# Ethernet_Phy.net
KiCad netlist of a schematic drawn in Altium Designer
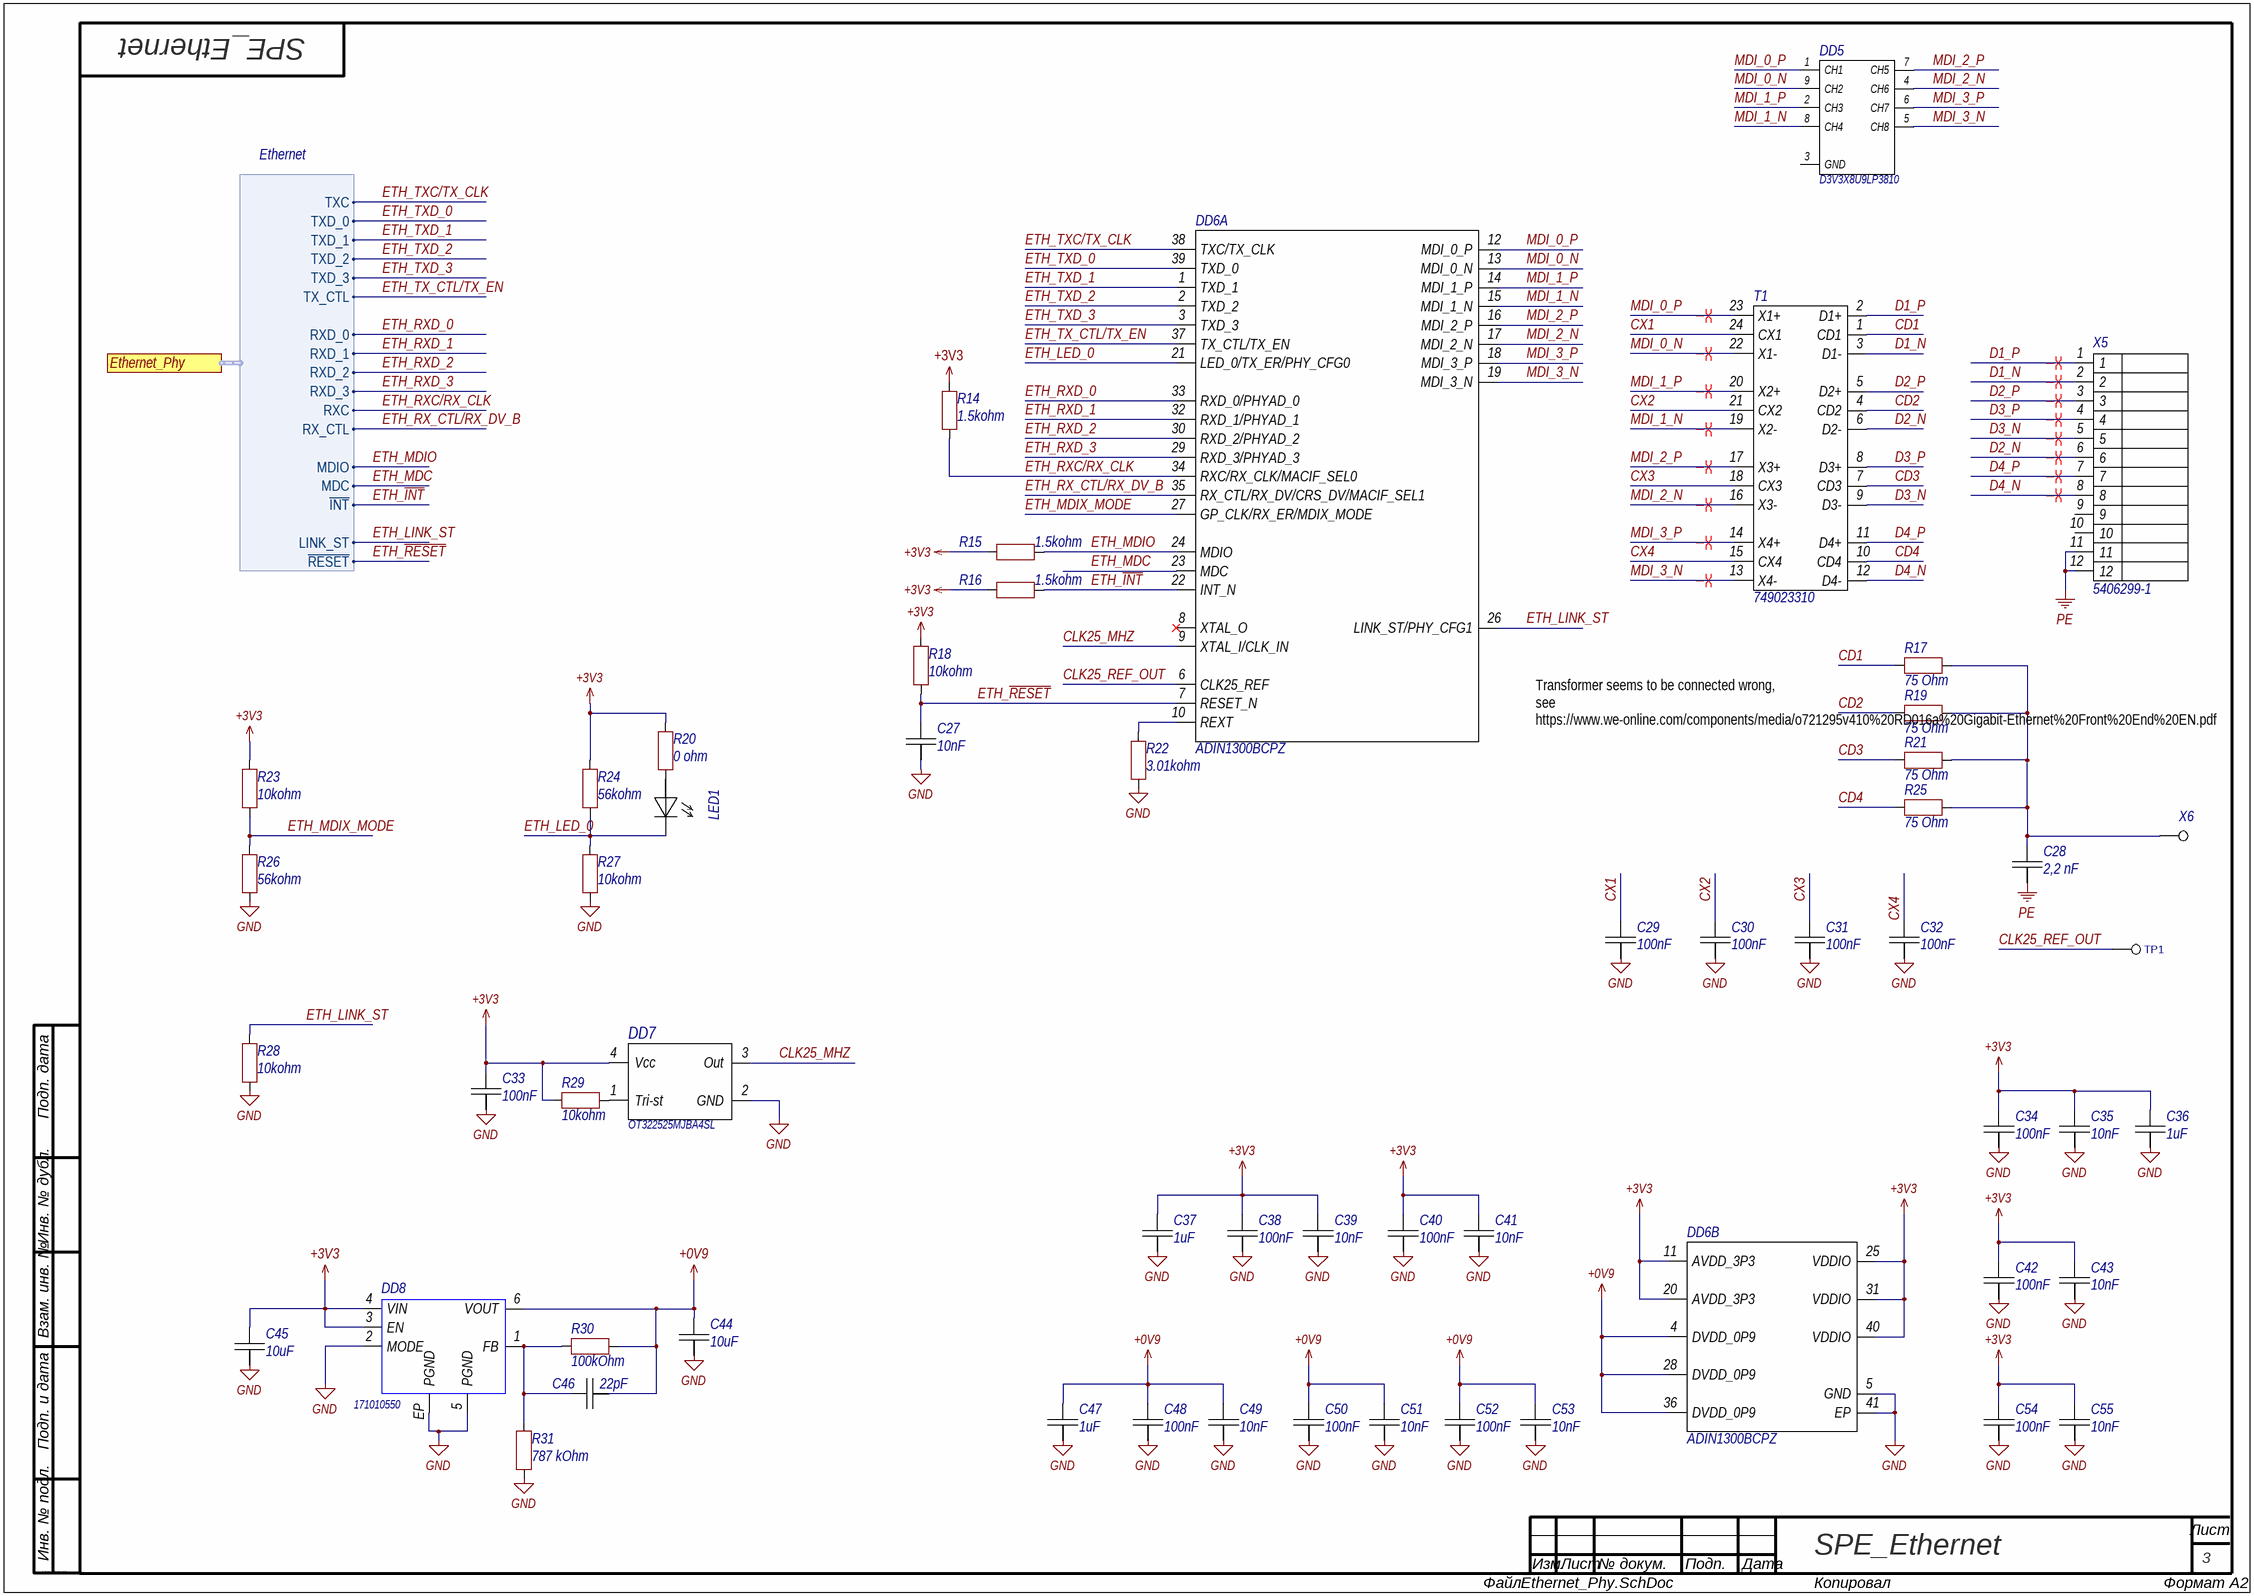
[diagram p0: Ethernet_Phy.SchDoc]

(export (version "E")
  (design (tool "Eeschema 10.0.6"))
  (components
    (comp (ref "C27")
      (value "10nF")
      (footprint "CAP0402")
      (fields
        (field (name "VOLTAGE") "50V")
        (field (name "PART NUMBER") "CAP0402")
        (field (name "Comment") "10nF 50V")
      )
      (libsource (lib "Library") (part "CAPC"))
    )
    (comp (ref "C28")
      (value "2,2 nF")
      (footprint "CAPC1206(3216)150_L")
      (fields
        (field (name "VOLTAGE") "2 kV")
        (field (name "PART NUMBER") "CAPC")
        (field (name "Comment") "2,2 nF 2 kV")
      )
      (libsource (lib "Library") (part "CAPC"))
    )
    (comp (ref "C29")
      (value "100nF")
      (footprint "CAP0402")
      (fields
        (field (name "VOLTAGE") "50V")
        (field (name "PART NUMBER") "CAP0402")
        (field (name "Comment") "100nF 50V")
      )
      (libsource (lib "Library") (part "CAPC"))
    )
    (comp (ref "C30")
      (value "100nF")
      (footprint "CAP0402")
      (fields
        (field (name "VOLTAGE") "50V")
        (field (name "PART NUMBER") "CAP0402")
        (field (name "Comment") "100nF 50V")
      )
      (libsource (lib "Library") (part "CAPC"))
    )
    (comp (ref "C31")
      (value "100nF")
      (footprint "CAP0402")
      (fields
        (field (name "VOLTAGE") "50V")
        (field (name "PART NUMBER") "CAP0402")
        (field (name "Comment") "100nF 50V")
      )
      (libsource (lib "Library") (part "CAPC"))
    )
    (comp (ref "C32")
      (value "100nF")
      (footprint "CAP0402")
      (fields
        (field (name "VOLTAGE") "50V")
        (field (name "PART NUMBER") "CAP0402")
        (field (name "Comment") "100nF 50V")
      )
      (libsource (lib "Library") (part "CAPC"))
    )
    (comp (ref "C33")
      (value "100nF")
      (footprint "CAP0402")
      (fields
        (field (name "VOLTAGE") "50V")
        (field (name "PART NUMBER") "CAP0402")
        (field (name "Comment") "100nF 50V")
      )
      (libsource (lib "Library") (part "CAPC"))
    )
    (comp (ref "C34")
      (value "100nF")
      (footprint "CAP0402")
      (fields
        (field (name "VOLTAGE") "50V")
        (field (name "PART NUMBER") "CAP0402")
        (field (name "Comment") "100nF 50V")
      )
      (libsource (lib "Library") (part "CAPC"))
    )
    (comp (ref "C35")
      (value "10nF")
      (footprint "CAP0402")
      (fields
        (field (name "VOLTAGE") "50V")
        (field (name "PART NUMBER") "CAP0402")
        (field (name "Comment") "10nF 50V")
      )
      (libsource (lib "Library") (part "CAPC"))
    )
    (comp (ref "C36")
      (value "1uF")
      (footprint "CAP0402")
      (fields
        (field (name "VOLTAGE") "25V")
        (field (name "PART NUMBER") "CAP0402")
        (field (name "Comment") "1uF 25V")
      )
      (libsource (lib "Library") (part "CAPC"))
    )
    (comp (ref "C37")
      (value "1uF")
      (footprint "CAP0402")
      (fields
        (field (name "VOLTAGE") "25V")
        (field (name "PART NUMBER") "CAP0402")
        (field (name "Comment") "1uF 25V")
      )
      (libsource (lib "Library") (part "CAPC"))
    )
    (comp (ref "C38")
      (value "100nF")
      (footprint "CAP0402")
      (fields
        (field (name "VOLTAGE") "50V")
        (field (name "PART NUMBER") "CAP0402")
        (field (name "Comment") "100nF 50V")
      )
      (libsource (lib "Library") (part "CAPC"))
    )
    (comp (ref "C39")
      (value "10nF")
      (footprint "CAP0402")
      (fields
        (field (name "VOLTAGE") "50V")
        (field (name "PART NUMBER") "CAP0402")
        (field (name "Comment") "10nF 50V")
      )
      (libsource (lib "Library") (part "CAPC"))
    )
    (comp (ref "C40")
      (value "100nF")
      (footprint "CAP0402")
      (fields
        (field (name "VOLTAGE") "50V")
        (field (name "PART NUMBER") "CAP0402")
        (field (name "Comment") "100nF 50V")
      )
      (libsource (lib "Library") (part "CAPC"))
    )
    (comp (ref "C41")
      (value "10nF")
      (footprint "CAP0402")
      (fields
        (field (name "VOLTAGE") "50V")
        (field (name "PART NUMBER") "CAP0402")
        (field (name "Comment") "10nF 50V")
      )
      (libsource (lib "Library") (part "CAPC"))
    )
    (comp (ref "C42")
      (value "100nF")
      (footprint "CAP0402")
      (fields
        (field (name "VOLTAGE") "50V")
        (field (name "PART NUMBER") "CAP0402")
        (field (name "Comment") "100nF 50V")
      )
      (libsource (lib "Library") (part "CAPC"))
    )
    (comp (ref "C43")
      (value "10nF")
      (footprint "CAP0402")
      (fields
        (field (name "VOLTAGE") "50V")
        (field (name "PART NUMBER") "CAP0402")
        (field (name "Comment") "10nF 50V")
      )
      (libsource (lib "Library") (part "CAPC"))
    )
    (comp (ref "C44")
      (value "10uF")
      (footprint "CAPC0603N")
      (fields
        (field (name "VOLTAGE") "25V")
        (field (name "PART NUMBER") "CAPC")
        (field (name "Comment") "10uF 25V")
      )
      (libsource (lib "Library") (part "CAPC"))
    )
    (comp (ref "C45")
      (value "10uF")
      (footprint "CAPC0603N")
      (fields
        (field (name "VOLTAGE") "25V")
        (field (name "PART NUMBER") "CAPC")
        (field (name "Comment") "10uF 25V")
      )
      (libsource (lib "Library") (part "CAPC"))
    )
    (comp (ref "C46")
      (value "22pF")
      (footprint "CAP0402")
      (fields
        (field (name "VOLTAGE") "50V")
        (field (name "PART NUMBER") "CAP0402")
        (field (name "Comment") "22pF 50V")
      )
      (libsource (lib "Library") (part "CAPC"))
    )
    (comp (ref "C47")
      (value "1uF")
      (footprint "CAP0402")
      (fields
        (field (name "VOLTAGE") "25V")
        (field (name "PART NUMBER") "CAP0402")
        (field (name "Comment") "1uF 25V")
      )
      (libsource (lib "Library") (part "CAPC"))
    )
    (comp (ref "C48")
      (value "100nF")
      (footprint "CAP0402")
      (fields
        (field (name "VOLTAGE") "50V")
        (field (name "PART NUMBER") "CAP0402")
        (field (name "Comment") "100nF 50V")
      )
      (libsource (lib "Library") (part "CAPC"))
    )
    (comp (ref "C49")
      (value "10nF")
      (footprint "CAP0402")
      (fields
        (field (name "VOLTAGE") "50V")
        (field (name "PART NUMBER") "CAP0402")
        (field (name "Comment") "10nF 50V")
      )
      (libsource (lib "Library") (part "CAPC"))
    )
    (comp (ref "C50")
      (value "100nF")
      (footprint "CAP0402")
      (fields
        (field (name "VOLTAGE") "50V")
        (field (name "PART NUMBER") "CAP0402")
        (field (name "Comment") "100nF 50V")
      )
      (libsource (lib "Library") (part "CAPC"))
    )
    (comp (ref "C51")
      (value "10nF")
      (footprint "CAP0402")
      (fields
        (field (name "VOLTAGE") "50V")
        (field (name "PART NUMBER") "CAP0402")
        (field (name "Comment") "10nF 50V")
      )
      (libsource (lib "Library") (part "CAPC"))
    )
    (comp (ref "C52")
      (value "100nF")
      (footprint "CAP0402")
      (fields
        (field (name "VOLTAGE") "50V")
        (field (name "PART NUMBER") "CAP0402")
        (field (name "Comment") "100nF 50V")
      )
      (libsource (lib "Library") (part "CAPC"))
    )
    (comp (ref "C53")
      (value "10nF")
      (footprint "CAP0402")
      (fields
        (field (name "VOLTAGE") "50V")
        (field (name "PART NUMBER") "CAP0402")
        (field (name "Comment") "10nF 50V")
      )
      (libsource (lib "Library") (part "CAPC"))
    )
    (comp (ref "C54")
      (value "100nF")
      (footprint "CAP0402")
      (fields
        (field (name "VOLTAGE") "50V")
        (field (name "PART NUMBER") "CAP0402")
        (field (name "Comment") "100nF 50V")
      )
      (libsource (lib "Library") (part "CAPC"))
    )
    (comp (ref "C55")
      (value "10nF")
      (footprint "CAP0402")
      (fields
        (field (name "VOLTAGE") "50V")
        (field (name "PART NUMBER") "CAP0402")
        (field (name "Comment") "10nF 50V")
      )
      (libsource (lib "Library") (part "CAPC"))
    )
    (comp (ref "DD5")
      (value "~")
      (footprint "U-DFN3810-9")
      (fields
        (field (name "MPN") "D3V3X8U9LP3810")
        (field (name "PART NUMBER") "D3V3X8U9LP3810")
        (field (name "MANUFACTURER") "DiodesInc")
      )
      (libsource (lib "Library") (part "DD_D3V3X8U9LP3810"))
    )
    (comp (ref "DD6")
      (value "~")
      (footprint "LFCSP-40")
      (fields
        (field (name "MPN") "ADIN1300BCPZ")
        (field (name "PART NUMBER") "ADIN1300BCPZ")
        (field (name "MANUFACTURER") "AD")
      )
      (libsource (lib "Library") (part "DD_ADIN1300"))
    )
    (comp (ref "DD7")
      (value "~")
      (footprint "TSX-3225_V")
      (fields
        (field (name "MPN") "OT322525MJBA4SL")
        (field (name "PART NUMBER") "OT322525MJBA4SL")
        (field (name "MANUFACTURER") "Yangxing Tech")
      )
      (libsource (lib "Library") (part "Crystal_oscillator"))
    )
    (comp (ref "DD8")
      (value "~")
      (footprint "171010550")
      (fields
        (field (name "MPN") "171010550")
        (field (name "PART NUMBER") "171010550")
        (field (name "MANUFACTURER") "WE")
      )
      (libsource (lib "Library") (part "171010550"))
    )
    (comp (ref "LED1")
      (value "Green")
      (footprint "LED0805")
      (fields (field (name "PART NUMBER") "LEDC0805"))
      (libsource (lib "Library") (part "LEDC"))
    )
    (comp (ref "R14")
      (value "1.5kohm")
      (footprint "RESC0402(1005)_M")
      (fields (field (name "PART NUMBER") "RES0402") (field (name "Comment") "1.5kohm "))
      (libsource (lib "Library") (part "RES"))
    )
    (comp (ref "R15")
      (value "1.5kohm")
      (footprint "RESC0402(1005)_M")
      (fields (field (name "PART NUMBER") "RES0402") (field (name "Comment") "1.5kohm "))
      (libsource (lib "") (part "RES_1"))
    )
    (comp (ref "R16")
      (value "1.5kohm")
      (footprint "RESC0402(1005)_M")
      (fields (field (name "PART NUMBER") "RES0402") (field (name "Comment") "1.5kohm "))
      (libsource (lib "") (part "RES_1"))
    )
    (comp (ref "R17")
      (value "75 Ohm")
      (footprint "RESC0603N")
      (fields (field (name "PART NUMBER") "RES") (field (name "Comment") "75 Ohm "))
      (libsource (lib "") (part "RES_2"))
    )
    (comp (ref "R18")
      (value "10kohm")
      (footprint "RESC0402(1005)_M")
      (fields (field (name "PART NUMBER") "RES0402") (field (name "Comment") "10kohm "))
      (libsource (lib "Library") (part "RES"))
    )
    (comp (ref "R19")
      (value "75 Ohm")
      (footprint "RESC0603N")
      (fields (field (name "PART NUMBER") "RES") (field (name "Comment") "75 Ohm "))
      (libsource (lib "") (part "RES_2"))
    )
    (comp (ref "R20")
      (value "0 ohm")
      (footprint "RESC0402(1005)_M")
      (fields (field (name "PART NUMBER") "RES0402") (field (name "Comment") "0 ohm "))
      (libsource (lib "Library") (part "RES"))
    )
    (comp (ref "R21")
      (value "75 Ohm")
      (footprint "RESC0603N")
      (fields (field (name "PART NUMBER") "RES") (field (name "Comment") "75 Ohm "))
      (libsource (lib "") (part "RES_2"))
    )
    (comp (ref "R22")
      (value "3.01kohm")
      (footprint "RESC0402(1005)_M")
      (fields
        (field (name "TOLERANCE") "1%")
        (field (name "PART NUMBER") "RES0402")
        (field (name "Comment") "3.01kohm ")
      )
      (libsource (lib "Library") (part "RES"))
    )
    (comp (ref "R23")
      (value "10kohm")
      (footprint "RESC0402(1005)_M")
      (fields (field (name "PART NUMBER") "RES0402") (field (name "Comment") "10kohm "))
      (libsource (lib "Library") (part "RES"))
    )
    (comp (ref "R24")
      (value "56kohm")
      (footprint "RESC0402(1005)_M")
      (fields (field (name "PART NUMBER") "RES0402") (field (name "Comment") "56kohm "))
      (libsource (lib "Library") (part "RES"))
    )
    (comp (ref "R25")
      (value "75 Ohm")
      (footprint "RESC0603N")
      (fields (field (name "PART NUMBER") "RES") (field (name "Comment") "75 Ohm "))
      (libsource (lib "") (part "RES_2"))
    )
    (comp (ref "R26")
      (value "56kohm")
      (footprint "RESC0402(1005)_M")
      (fields (field (name "PART NUMBER") "RES0402") (field (name "Comment") "56kohm "))
      (libsource (lib "Library") (part "RES"))
    )
    (comp (ref "R27")
      (value "10kohm")
      (footprint "RESC0402(1005)_M")
      (fields (field (name "PART NUMBER") "RES0402") (field (name "Comment") "10kohm "))
      (libsource (lib "Library") (part "RES"))
    )
    (comp (ref "R28")
      (value "10kohm")
      (footprint "RESC0402(1005)_M")
      (fields (field (name "PART NUMBER") "RES0402") (field (name "Comment") "10kohm "))
      (libsource (lib "Library") (part "RES"))
    )
    (comp (ref "R29")
      (value "10kohm")
      (footprint "RESC0402(1005)_M")
      (fields (field (name "PART NUMBER") "RES0402") (field (name "Comment") "10kohm "))
      (libsource (lib "") (part "RES_1"))
    )
    (comp (ref "R30")
      (value "100kOhm")
      (footprint "RESC0402(1005)_M")
      (fields (field (name "PART NUMBER") "RES0402") (field (name "Comment") "100kOhm "))
      (libsource (lib "") (part "RES_2"))
    )
    (comp (ref "R31")
      (value "787 kOhm")
      (footprint "RESC0805L")
      (fields (field (name "PART NUMBER") "RES") (field (name "Comment") "787 kOhm "))
      (libsource (lib "Library") (part "RES"))
    )
    (comp (ref "T1")
      (value "180 uH")
      (footprint "749023310")
      (description "WE-LAN AQ SMT Transformer, 1000 Base-T, PoE (up to 350 mA), 180uH")
      (fields
        (field (name "MPN") "749023310")
        (field (name "PART NUMBER") "749023310")
        (field (name "MANUFACTURER") "WE")
      )
      (libsource (lib "Library") (part "749023310"))
    )
    (comp (ref "TP1")
      (value "TP-SINGLE-ROUND")
      (footprint "TP-ROUND-TOP-1.5")
      (libsource (lib "Library") (part "TP-SINGLE-ROUND"))
    )
    (comp (ref "X5")
      (value "5406299-1")
      (footprint "RJ-45_5406299-1")
      (fields (field (name "MPN") "5406299-1") (field (name "MANUFACTURER") "TE"))
      (libsource (lib "Library") (part "Connector_12pin"))
    )
    (comp (ref "X6")
      (value "PLS1")
      (footprint "PLS1")
      (fields (field (name "PART NUMBER") "Test_PLS1"))
      (libsource (lib "Library") (part "PAD-CONNECT-MINI"))
    )
  )
  (nets
    (net (code "2") (name "+0V9") (class "Default")
      (node (ref "C44") (pin "2") (pinfunction "2_2") (pintype "passive"))
      (node (ref "C46") (pin "1") (pinfunction "1_1") (pintype "passive"))
      (node (ref "C47") (pin "2") (pinfunction "2_2") (pintype "passive"))
      (node (ref "C48") (pin "2") (pinfunction "2_2") (pintype "passive"))
      (node (ref "C49") (pin "2") (pinfunction "2_2") (pintype "passive"))
      (node (ref "C50") (pin "2") (pinfunction "2_2") (pintype "passive"))
      (node (ref "C51") (pin "2") (pinfunction "2_2") (pintype "passive"))
      (node (ref "C52") (pin "2") (pinfunction "2_2") (pintype "passive"))
      (node (ref "C53") (pin "2") (pinfunction "2_2") (pintype "passive"))
      (node (ref "DD6") (pin "28") (pinfunction "DVDD_0P9_28") (pintype "passive"))
      (node (ref "DD6") (pin "36") (pinfunction "DVDD_0P9_36") (pintype "passive"))
      (node (ref "DD6") (pin "4") (pinfunction "DVDD_0P9_4") (pintype "passive"))
      (node (ref "DD8") (pin "6") (pinfunction "VOUT_6") (pintype "passive"))
      (node (ref "R30") (pin "1") (pinfunction "1_1") (pintype "passive"))
    )
    (net (code "3") (name "+3V3") (class "Default")
      (node (ref "C33") (pin "2") (pinfunction "2_2") (pintype "passive"))
      (node (ref "C34") (pin "2") (pinfunction "2_2") (pintype "passive"))
      (node (ref "C35") (pin "2") (pinfunction "2_2") (pintype "passive"))
      (node (ref "C36") (pin "2") (pinfunction "2_2") (pintype "passive"))
      (node (ref "C37") (pin "2") (pinfunction "2_2") (pintype "passive"))
      (node (ref "C38") (pin "2") (pinfunction "2_2") (pintype "passive"))
      (node (ref "C39") (pin "2") (pinfunction "2_2") (pintype "passive"))
      (node (ref "C40") (pin "2") (pinfunction "2_2") (pintype "passive"))
      (node (ref "C41") (pin "2") (pinfunction "2_2") (pintype "passive"))
      (node (ref "C42") (pin "2") (pinfunction "2_2") (pintype "passive"))
      (node (ref "C43") (pin "2") (pinfunction "2_2") (pintype "passive"))
      (node (ref "C45") (pin "2") (pinfunction "2_2") (pintype "passive"))
      (node (ref "C54") (pin "2") (pinfunction "2_2") (pintype "passive"))
      (node (ref "C55") (pin "2") (pinfunction "2_2") (pintype "passive"))
      (node (ref "DD6") (pin "11") (pinfunction "AVDD_3P3_11") (pintype "passive"))
      (node (ref "DD6") (pin "20") (pinfunction "AVDD_3P3_20") (pintype "passive"))
      (node (ref "DD6") (pin "25") (pinfunction "VDDIO_25") (pintype "passive"))
      (node (ref "DD6") (pin "31") (pinfunction "VDDIO_31") (pintype "passive"))
      (node (ref "DD6") (pin "40") (pinfunction "VDDIO_40") (pintype "passive"))
      (node (ref "DD7") (pin "4") (pinfunction "Vcc_4") (pintype "passive"))
      (node (ref "DD8") (pin "3") (pinfunction "EN_3") (pintype "passive"))
      (node (ref "DD8") (pin "4") (pinfunction "VIN_4") (pintype "passive"))
      (node (ref "R14") (pin "2") (pinfunction "2_2") (pintype "passive"))
      (node (ref "R15") (pin "1") (pinfunction "1_1") (pintype "passive"))
      (node (ref "R16") (pin "1") (pinfunction "1_1") (pintype "passive"))
      (node (ref "R18") (pin "2") (pinfunction "2_2") (pintype "passive"))
      (node (ref "R20") (pin "2") (pinfunction "2_2") (pintype "passive"))
      (node (ref "R23") (pin "2") (pinfunction "2_2") (pintype "passive"))
      (node (ref "R24") (pin "2") (pinfunction "2_2") (pintype "passive"))
      (node (ref "R29") (pin "1") (pinfunction "1_1") (pintype "passive"))
    )
    (net (code "4") (name "/CD1") (class "Default")
      (node (ref "R17") (pin "2") (pinfunction "2_2") (pintype "passive"))
      (node (ref "T1") (pin "1") (pinfunction "CD1_1") (pintype "passive"))
    )
    (net (code "5") (name "/CD2") (class "Default")
      (node (ref "R19") (pin "2") (pinfunction "2_2") (pintype "passive"))
      (node (ref "T1") (pin "4") (pinfunction "CD2_4") (pintype "passive"))
    )
    (net (code "6") (name "/CD3") (class "Default")
      (node (ref "R21") (pin "2") (pinfunction "2_2") (pintype "passive"))
      (node (ref "T1") (pin "7") (pinfunction "CD3_7") (pintype "passive"))
    )
    (net (code "7") (name "/CD4") (class "Default")
      (node (ref "R25") (pin "2") (pinfunction "2_2") (pintype "passive"))
      (node (ref "T1") (pin "10") (pinfunction "CD4_10") (pintype "passive"))
    )
    (net (code "8") (name "/CLK25_MHZ") (class "Default")
      (node (ref "DD6") (pin "9") (pinfunction "XTAL_I/CLK_IN_9") (pintype "passive"))
      (node (ref "DD7") (pin "3") (pinfunction "Out_3") (pintype "passive"))
    )
    (net (code "9") (name "/CLK25_REF_OUT") (class "Default")
      (node (ref "DD6") (pin "6") (pinfunction "CLK25_REF_6") (pintype "passive"))
      (node (ref "TP1") (pin "1") (pinfunction "1_1") (pintype "passive"))
    )
    (net (code "10") (name "/CX1") (class "Default")
      (node (ref "C29") (pin "2") (pinfunction "2_2") (pintype "passive"))
      (node (ref "T1") (pin "24") (pinfunction "CX1_24") (pintype "passive"))
    )
    (net (code "11") (name "/CX2") (class "Default")
      (node (ref "C30") (pin "2") (pinfunction "2_2") (pintype "passive"))
      (node (ref "T1") (pin "21") (pinfunction "CX2_21") (pintype "passive"))
    )
    (net (code "12") (name "/CX3") (class "Default")
      (node (ref "C31") (pin "2") (pinfunction "2_2") (pintype "passive"))
      (node (ref "T1") (pin "18") (pinfunction "CX3_18") (pintype "passive"))
    )
    (net (code "13") (name "/CX4") (class "Default")
      (node (ref "C32") (pin "2") (pinfunction "2_2") (pintype "passive"))
      (node (ref "T1") (pin "15") (pinfunction "CX4_15") (pintype "passive"))
    )
    (net (code "14") (name "/D1_N") (class "Default")
      (node (ref "T1") (pin "3") (pinfunction "D1-_3") (pintype "passive"))
      (node (ref "X5") (pin "2") (pinfunction "2_2") (pintype "passive"))
    )
    (net (code "15") (name "/D1_P") (class "Default")
      (node (ref "T1") (pin "2") (pinfunction "D1+_2") (pintype "passive"))
      (node (ref "X5") (pin "1") (pinfunction "1_1") (pintype "passive"))
    )
    (net (code "16") (name "/D2_N") (class "Default")
      (node (ref "T1") (pin "6") (pinfunction "D2-_6") (pintype "passive"))
      (node (ref "X5") (pin "6") (pinfunction "6_6") (pintype "passive"))
    )
    (net (code "17") (name "/D2_P") (class "Default")
      (node (ref "T1") (pin "5") (pinfunction "D2+_5") (pintype "passive"))
      (node (ref "X5") (pin "3") (pinfunction "3_3") (pintype "passive"))
    )
    (net (code "18") (name "/D3_N") (class "Default")
      (node (ref "T1") (pin "9") (pinfunction "D3-_9") (pintype "passive"))
      (node (ref "X5") (pin "5") (pinfunction "5_5") (pintype "passive"))
    )
    (net (code "19") (name "/D3_P") (class "Default")
      (node (ref "T1") (pin "8") (pinfunction "D3+_8") (pintype "passive"))
      (node (ref "X5") (pin "4") (pinfunction "4_4") (pintype "passive"))
    )
    (net (code "20") (name "/D4_N") (class "Default")
      (node (ref "T1") (pin "12") (pinfunction "D4-_12") (pintype "passive"))
      (node (ref "X5") (pin "8") (pinfunction "8_8") (pintype "passive"))
    )
    (net (code "21") (name "/D4_P") (class "Default")
      (node (ref "T1") (pin "11") (pinfunction "D4+_11") (pintype "passive"))
      (node (ref "X5") (pin "7") (pinfunction "7_7") (pintype "passive"))
    )
    (net (code "22") (name "/ETH_LED_0") (class "Default")
      (node (ref "DD6") (pin "21") (pinfunction "LED_0/TX_ER/PHY_CFG0_21") (pintype "passive"))
      (node (ref "LED1") (pin "1") (pinfunction "A_1") (pintype "passive"))
      (node (ref "R24") (pin "1") (pinfunction "1_1") (pintype "passive"))
      (node (ref "R27") (pin "2") (pinfunction "2_2") (pintype "passive"))
    )
    (net (code "23") (name "/ETH_LINK_ST") (class "Default")
      (node (ref "DD6") (pin "26") (pinfunction "LINK_ST/PHY_CFG1_26") (pintype "passive"))
      (node (ref "R28") (pin "2") (pinfunction "2_2") (pintype "passive"))
    )
    (net (code "24") (name "/ETH_MDC") (class "Default")
      (node (ref "DD6") (pin "23") (pinfunction "MDC_23") (pintype "passive"))
    )
    (net (code "25") (name "/ETH_MDIO") (class "Default")
      (node (ref "DD6") (pin "24") (pinfunction "MDIO_24") (pintype "passive"))
      (node (ref "R15") (pin "2") (pinfunction "2_2") (pintype "passive"))
    )
    (net (code "26") (name "/ETH_MDIX_MODE") (class "Default")
      (node (ref "DD6") (pin "27") (pinfunction "GP_CLK/RX_ER/MDIX_MODE_27") (pintype "passive"))
      (node (ref "R23") (pin "1") (pinfunction "1_1") (pintype "passive"))
      (node (ref "R26") (pin "2") (pinfunction "2_2") (pintype "passive"))
    )
    (net (code "27") (name "/ETH_RXC{slash}RX_CLK") (class "Default")
      (node (ref "DD6") (pin "34") (pinfunction "RXC/RX_CLK/MACIF_SEL0_34") (pintype "passive"))
      (node (ref "R14") (pin "1") (pinfunction "1_1") (pintype "passive"))
    )
    (net (code "28") (name "/ETH_RXD_0") (class "Default")
      (node (ref "DD6") (pin "33") (pinfunction "RXD_0/PHYAD_0_33") (pintype "passive"))
    )
    (net (code "29") (name "/ETH_RXD_1") (class "Default")
      (node (ref "DD6") (pin "32") (pinfunction "RXD_1/PHYAD_1_32") (pintype "passive"))
    )
    (net (code "30") (name "/ETH_RXD_2") (class "Default")
      (node (ref "DD6") (pin "30") (pinfunction "RXD_2/PHYAD_2_30") (pintype "passive"))
    )
    (net (code "31") (name "/ETH_RXD_3") (class "Default")
      (node (ref "DD6") (pin "29") (pinfunction "RXD_3/PHYAD_3_29") (pintype "passive"))
    )
    (net (code "32") (name "/ETH_RX_CTL{slash}RX_DV_B") (class "Default")
      (node (ref "DD6") (pin "35") (pinfunction "RX_CTL/RX_DV/CRS_DV/MACIF_SEL1_35") (pintype "passive"))
    )
    (net (code "33") (name "/ETH_TXC{slash}TX_CLK") (class "Default")
      (node (ref "DD6") (pin "38") (pinfunction "TXC/TX_CLK_38") (pintype "passive"))
    )
    (net (code "34") (name "/ETH_TXD_0") (class "Default")
      (node (ref "DD6") (pin "39") (pinfunction "TXD_0_39") (pintype "passive"))
    )
    (net (code "35") (name "/ETH_TXD_1") (class "Default")
      (node (ref "DD6") (pin "1") (pinfunction "TXD_1_1") (pintype "passive"))
    )
    (net (code "36") (name "/ETH_TXD_2") (class "Default")
      (node (ref "DD6") (pin "2") (pinfunction "TXD_2_2") (pintype "passive"))
    )
    (net (code "37") (name "/ETH_TXD_3") (class "Default")
      (node (ref "DD6") (pin "3") (pinfunction "TXD_3_3") (pintype "passive"))
    )
    (net (code "38") (name "/ETH_TX_CTL{slash}TX_EN") (class "Default")
      (node (ref "DD6") (pin "37") (pinfunction "TX_CTL/TX_EN_37") (pintype "passive"))
    )
    (net (code "39") (name "/ETH_~{INT}") (class "Default")
      (node (ref "DD6") (pin "22") (pinfunction "INT_N_22") (pintype "passive"))
      (node (ref "R16") (pin "2") (pinfunction "2_2") (pintype "passive"))
    )
    (net (code "40") (name "/ETH_~{RESET}") (class "Default")
      (node (ref "C27") (pin "2") (pinfunction "2_2") (pintype "passive"))
      (node (ref "DD6") (pin "7") (pinfunction "RESET_N_7") (pintype "passive"))
      (node (ref "R18") (pin "1") (pinfunction "1_1") (pintype "passive"))
    )
    (net (code "41") (name "/MDI_0_N") (class "Default")
      (node (ref "DD5") (pin "9") (pinfunction "CH2_9") (pintype "passive"))
      (node (ref "DD6") (pin "13") (pinfunction "MDI_0_N_13") (pintype "passive"))
      (node (ref "T1") (pin "22") (pinfunction "X1-_22") (pintype "passive"))
    )
    (net (code "42") (name "/MDI_0_P") (class "Default")
      (node (ref "DD5") (pin "1") (pinfunction "CH1_1") (pintype "passive"))
      (node (ref "DD6") (pin "12") (pinfunction "MDI_0_P_12") (pintype "passive"))
      (node (ref "T1") (pin "23") (pinfunction "X1+_23") (pintype "passive"))
    )
    (net (code "43") (name "/MDI_1_N") (class "Default")
      (node (ref "DD5") (pin "8") (pinfunction "CH4_8") (pintype "passive"))
      (node (ref "DD6") (pin "15") (pinfunction "MDI_1_N_15") (pintype "passive"))
      (node (ref "T1") (pin "19") (pinfunction "X2-_19") (pintype "passive"))
    )
    (net (code "44") (name "/MDI_1_P") (class "Default")
      (node (ref "DD5") (pin "2") (pinfunction "CH3_2") (pintype "passive"))
      (node (ref "DD6") (pin "14") (pinfunction "MDI_1_P_14") (pintype "passive"))
      (node (ref "T1") (pin "20") (pinfunction "X2+_20") (pintype "passive"))
    )
    (net (code "45") (name "/MDI_2_N") (class "Default")
      (node (ref "DD5") (pin "4") (pinfunction "CH6_4") (pintype "passive"))
      (node (ref "DD6") (pin "17") (pinfunction "MDI_2_N_17") (pintype "passive"))
      (node (ref "T1") (pin "16") (pinfunction "X3-_16") (pintype "passive"))
    )
    (net (code "46") (name "/MDI_2_P") (class "Default")
      (node (ref "DD5") (pin "7") (pinfunction "CH5_7") (pintype "passive"))
      (node (ref "DD6") (pin "16") (pinfunction "MDI_2_P_16") (pintype "passive"))
      (node (ref "T1") (pin "17") (pinfunction "X3+_17") (pintype "passive"))
    )
    (net (code "47") (name "/MDI_3_N") (class "Default")
      (node (ref "DD5") (pin "5") (pinfunction "CH8_5") (pintype "passive"))
      (node (ref "DD6") (pin "19") (pinfunction "MDI_3_N_19") (pintype "passive"))
      (node (ref "T1") (pin "13") (pinfunction "X4-_13") (pintype "passive"))
    )
    (net (code "48") (name "/MDI_3_P") (class "Default")
      (node (ref "DD5") (pin "6") (pinfunction "CH7_6") (pintype "passive"))
      (node (ref "DD6") (pin "18") (pinfunction "MDI_3_P_18") (pintype "passive"))
      (node (ref "T1") (pin "14") (pinfunction "X4+_14") (pintype "passive"))
    )
    (net (code "50") (name "GND") (class "Default")
      (node (ref "C27") (pin "1") (pinfunction "1_1") (pintype "passive"))
      (node (ref "C29") (pin "1") (pinfunction "1_1") (pintype "passive"))
      (node (ref "C30") (pin "1") (pinfunction "1_1") (pintype "passive"))
      (node (ref "C31") (pin "1") (pinfunction "1_1") (pintype "passive"))
      (node (ref "C32") (pin "1") (pinfunction "1_1") (pintype "passive"))
      (node (ref "C33") (pin "1") (pinfunction "1_1") (pintype "passive"))
      (node (ref "C34") (pin "1") (pinfunction "1_1") (pintype "passive"))
      (node (ref "C35") (pin "1") (pinfunction "1_1") (pintype "passive"))
      (node (ref "C36") (pin "1") (pinfunction "1_1") (pintype "passive"))
      (node (ref "C37") (pin "1") (pinfunction "1_1") (pintype "passive"))
      (node (ref "C38") (pin "1") (pinfunction "1_1") (pintype "passive"))
      (node (ref "C39") (pin "1") (pinfunction "1_1") (pintype "passive"))
      (node (ref "C40") (pin "1") (pinfunction "1_1") (pintype "passive"))
      (node (ref "C41") (pin "1") (pinfunction "1_1") (pintype "passive"))
      (node (ref "C42") (pin "1") (pinfunction "1_1") (pintype "passive"))
      (node (ref "C43") (pin "1") (pinfunction "1_1") (pintype "passive"))
      (node (ref "C44") (pin "1") (pinfunction "1_1") (pintype "passive"))
      (node (ref "C45") (pin "1") (pinfunction "1_1") (pintype "passive"))
      (node (ref "C47") (pin "1") (pinfunction "1_1") (pintype "passive"))
      (node (ref "C48") (pin "1") (pinfunction "1_1") (pintype "passive"))
      (node (ref "C49") (pin "1") (pinfunction "1_1") (pintype "passive"))
      (node (ref "C50") (pin "1") (pinfunction "1_1") (pintype "passive"))
      (node (ref "C51") (pin "1") (pinfunction "1_1") (pintype "passive"))
      (node (ref "C52") (pin "1") (pinfunction "1_1") (pintype "passive"))
      (node (ref "C53") (pin "1") (pinfunction "1_1") (pintype "passive"))
      (node (ref "C54") (pin "1") (pinfunction "1_1") (pintype "passive"))
      (node (ref "C55") (pin "1") (pinfunction "1_1") (pintype "passive"))
      (node (ref "DD6") (pin "41") (pinfunction "EP_41") (pintype "passive"))
      (node (ref "DD6") (pin "5") (pinfunction "GND_5") (pintype "passive"))
      (node (ref "DD7") (pin "2") (pinfunction "GND_2") (pintype "passive"))
      (node (ref "DD8") (pin "2") (pinfunction "MODE_2") (pintype "passive"))
      (node (ref "DD8") (pin "5") (pinfunction "PGND_5") (pintype "passive"))
      (node (ref "DD8") (pin "EP") (pinfunction "PGND_EP") (pintype "passive"))
      (node (ref "R22") (pin "1") (pinfunction "1_1") (pintype "passive"))
      (node (ref "R26") (pin "1") (pinfunction "1_1") (pintype "passive"))
      (node (ref "R27") (pin "1") (pinfunction "1_1") (pintype "passive"))
      (node (ref "R28") (pin "1") (pinfunction "1_1") (pintype "passive"))
      (node (ref "R31") (pin "1") (pinfunction "1_1") (pintype "passive"))
    )
    (net (code "51") (name "Net-(C28-Pad2)") (class "Default")
      (node (ref "C28") (pin "2") (pinfunction "2_2") (pintype "passive"))
      (node (ref "R17") (pin "1") (pinfunction "1_1") (pintype "passive"))
      (node (ref "R19") (pin "1") (pinfunction "1_1") (pintype "passive"))
      (node (ref "R21") (pin "1") (pinfunction "1_1") (pintype "passive"))
      (node (ref "R25") (pin "1") (pinfunction "1_1") (pintype "passive"))
      (node (ref "X6") (pin "1") (pinfunction "1_1") (pintype "passive"))
    )
    (net (code "52") (name "Net-(DD6A-REXT)") (class "Default")
      (node (ref "DD6") (pin "10") (pinfunction "REXT_10") (pintype "passive"))
      (node (ref "R22") (pin "2") (pinfunction "2_2") (pintype "passive"))
    )
    (net (code "53") (name "Net-(DD7-Tri-st)") (class "Default")
      (node (ref "DD7") (pin "1") (pinfunction "Tri-st_1") (pintype "passive"))
      (node (ref "R29") (pin "2") (pinfunction "2_2") (pintype "passive"))
    )
    (net (code "54") (name "Net-(DD8-FB)") (class "Default")
      (node (ref "C46") (pin "2") (pinfunction "2_2") (pintype "passive"))
      (node (ref "DD8") (pin "1") (pinfunction "FB_1") (pintype "passive"))
      (node (ref "R30") (pin "2") (pinfunction "2_2") (pintype "passive"))
      (node (ref "R31") (pin "2") (pinfunction "2_2") (pintype "passive"))
    )
    (net (code "55") (name "Net-(LED1-K)") (class "Default")
      (node (ref "LED1") (pin "2") (pinfunction "K_2") (pintype "passive"))
      (node (ref "R20") (pin "1") (pinfunction "1_1") (pintype "passive"))
    )
    (net (code "56") (name "PE") (class "Default")
      (node (ref "C28") (pin "1") (pinfunction "1_1") (pintype "passive"))
      (node (ref "X5") (pin "11") (pinfunction "11_11") (pintype "passive"))
      (node (ref "X5") (pin "12") (pinfunction "12_12") (pintype "passive"))
    )
    (net (code "57") (name "unconnected-(DD5-GND-Pad3)") (class "Default")
      (node (ref "DD5") (pin "3") (pinfunction "GND_3") (pintype "passive"))
    )
    (net (code "58") (name "unconnected-(DD6A-XTAL_O-Pad8)") (class "Default")
      (node (ref "DD6") (pin "8") (pinfunction "XTAL_O_8") (pintype "passive+no_connect"))
    )
    (net (code "59") (name "unconnected-(X5-Pad9)") (class "Default")
      (node (ref "X5") (pin "9") (pinfunction "9_9") (pintype "passive"))
    )
    (net (code "60") (name "unconnected-(X5-Pad10)") (class "Default")
      (node (ref "X5") (pin "10") (pinfunction "10_10") (pintype "passive"))
    )
  )
)
